# SCH_08_InOut_Terminal.net
KiCad netlist of a schematic drawn in Altium Designer
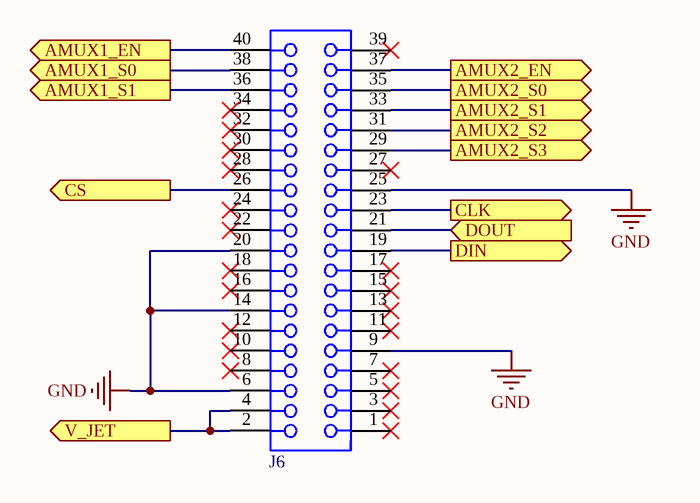
[diagram p0: SCH_08_InOut_Terminal.SchDoc]

(export (version "E")
  (design (tool "Eeschema 10.0.6"))
  (components
    (comp (ref "J6")
      (value "61304021821")
      (footprint "61304021821")
      (description "WR-PHD Socket Header, THT, Vertical, pitch 2.54mm, 2 Row, 40P")
      (fields (field (name "MANUFACTURER") "Wurth Elektronik"))
      (libsource (lib "Altium_WR-PHD (rev24a)") (part "61304021821"))
    )
  )
  (nets
    (net (code "1") (name "/AMUX1_EN") (class "Default")
      (node (ref "J6") (pin "40") (pinfunction "40_40") (pintype "passive"))
    )
    (net (code "2") (name "/AMUX1_S0") (class "Default")
      (node (ref "J6") (pin "38") (pinfunction "38_38") (pintype "passive"))
    )
    (net (code "3") (name "/AMUX1_S1") (class "Default")
      (node (ref "J6") (pin "36") (pinfunction "36_36") (pintype "passive"))
    )
    (net (code "4") (name "/AMUX2_EN") (class "Default")
      (node (ref "J6") (pin "37") (pinfunction "37_37") (pintype "passive"))
    )
    (net (code "5") (name "/AMUX2_S0") (class "Default")
      (node (ref "J6") (pin "35") (pinfunction "35_35") (pintype "passive"))
    )
    (net (code "6") (name "/AMUX2_S1") (class "Default")
      (node (ref "J6") (pin "33") (pinfunction "33_33") (pintype "passive"))
    )
    (net (code "7") (name "/AMUX2_S2") (class "Default")
      (node (ref "J6") (pin "31") (pinfunction "31_31") (pintype "passive"))
    )
    (net (code "8") (name "/AMUX2_S3") (class "Default")
      (node (ref "J6") (pin "29") (pinfunction "29_29") (pintype "passive"))
    )
    (net (code "9") (name "/CLK") (class "Default")
      (node (ref "J6") (pin "23") (pinfunction "23_23") (pintype "passive"))
    )
    (net (code "10") (name "/CS") (class "Default")
      (node (ref "J6") (pin "26") (pinfunction "26_26") (pintype "passive"))
    )
    (net (code "11") (name "/DIN") (class "Default")
      (node (ref "J6") (pin "19") (pinfunction "19_19") (pintype "passive"))
    )
    (net (code "12") (name "/DOUT") (class "Default")
      (node (ref "J6") (pin "21") (pinfunction "21_21") (pintype "passive"))
    )
    (net (code "13") (name "/V_JET") (class "Default")
      (node (ref "J6") (pin "2") (pinfunction "2_2") (pintype "passive"))
      (node (ref "J6") (pin "4") (pinfunction "4_4") (pintype "passive"))
    )
    (net (code "14") (name "GND") (class "Default")
      (node (ref "J6") (pin "14") (pinfunction "14_14") (pintype "passive"))
      (node (ref "J6") (pin "20") (pinfunction "20_20") (pintype "passive"))
      (node (ref "J6") (pin "25") (pinfunction "25_25") (pintype "passive"))
      (node (ref "J6") (pin "6") (pinfunction "6_6") (pintype "passive"))
      (node (ref "J6") (pin "9") (pinfunction "9_9") (pintype "passive"))
    )
    (net (code "15") (name "unconnected-(J6-Pad1)") (class "Default")
      (node (ref "J6") (pin "1") (pinfunction "1_1") (pintype "passive+no_connect"))
    )
    (net (code "16") (name "unconnected-(J6-Pad3)") (class "Default")
      (node (ref "J6") (pin "3") (pinfunction "3_3") (pintype "passive+no_connect"))
    )
    (net (code "17") (name "unconnected-(J6-Pad5)") (class "Default")
      (node (ref "J6") (pin "5") (pinfunction "5_5") (pintype "passive+no_connect"))
    )
    (net (code "18") (name "unconnected-(J6-Pad7)") (class "Default")
      (node (ref "J6") (pin "7") (pinfunction "7_7") (pintype "passive+no_connect"))
    )
    (net (code "19") (name "unconnected-(J6-Pad8)") (class "Default")
      (node (ref "J6") (pin "8") (pinfunction "8_8") (pintype "passive+no_connect"))
    )
    (net (code "20") (name "unconnected-(J6-Pad10)") (class "Default")
      (node (ref "J6") (pin "10") (pinfunction "10_10") (pintype "passive+no_connect"))
    )
    (net (code "21") (name "unconnected-(J6-Pad11)") (class "Default")
      (node (ref "J6") (pin "11") (pinfunction "11_11") (pintype "passive+no_connect"))
    )
    (net (code "22") (name "unconnected-(J6-Pad12)") (class "Default")
      (node (ref "J6") (pin "12") (pinfunction "12_12") (pintype "passive+no_connect"))
    )
    (net (code "23") (name "unconnected-(J6-Pad13)") (class "Default")
      (node (ref "J6") (pin "13") (pinfunction "13_13") (pintype "passive+no_connect"))
    )
    (net (code "24") (name "unconnected-(J6-Pad15)") (class "Default")
      (node (ref "J6") (pin "15") (pinfunction "15_15") (pintype "passive+no_connect"))
    )
    (net (code "25") (name "unconnected-(J6-Pad16)") (class "Default")
      (node (ref "J6") (pin "16") (pinfunction "16_16") (pintype "passive+no_connect"))
    )
    (net (code "26") (name "unconnected-(J6-Pad17)") (class "Default")
      (node (ref "J6") (pin "17") (pinfunction "17_17") (pintype "passive+no_connect"))
    )
    (net (code "27") (name "unconnected-(J6-Pad18)") (class "Default")
      (node (ref "J6") (pin "18") (pinfunction "18_18") (pintype "passive+no_connect"))
    )
    (net (code "28") (name "unconnected-(J6-Pad22)") (class "Default")
      (node (ref "J6") (pin "22") (pinfunction "22_22") (pintype "passive+no_connect"))
    )
    (net (code "29") (name "unconnected-(J6-Pad24)") (class "Default")
      (node (ref "J6") (pin "24") (pinfunction "24_24") (pintype "passive+no_connect"))
    )
    (net (code "30") (name "unconnected-(J6-Pad27)") (class "Default")
      (node (ref "J6") (pin "27") (pinfunction "27_27") (pintype "passive+no_connect"))
    )
    (net (code "31") (name "unconnected-(J6-Pad28)") (class "Default")
      (node (ref "J6") (pin "28") (pinfunction "28_28") (pintype "passive+no_connect"))
    )
    (net (code "32") (name "unconnected-(J6-Pad30)") (class "Default")
      (node (ref "J6") (pin "30") (pinfunction "30_30") (pintype "passive+no_connect"))
    )
    (net (code "33") (name "unconnected-(J6-Pad32)") (class "Default")
      (node (ref "J6") (pin "32") (pinfunction "32_32") (pintype "passive+no_connect"))
    )
    (net (code "34") (name "unconnected-(J6-Pad34)") (class "Default")
      (node (ref "J6") (pin "34") (pinfunction "34_34") (pintype "passive+no_connect"))
    )
    (net (code "35") (name "unconnected-(J6-Pad39)") (class "Default")
      (node (ref "J6") (pin "39") (pinfunction "39_39") (pintype "passive+no_connect"))
    )
  )
)
